# jeu_du_moulin_boura_TouchPAD_SCH.net
KiCad netlist of a schematic drawn in Altium Designer
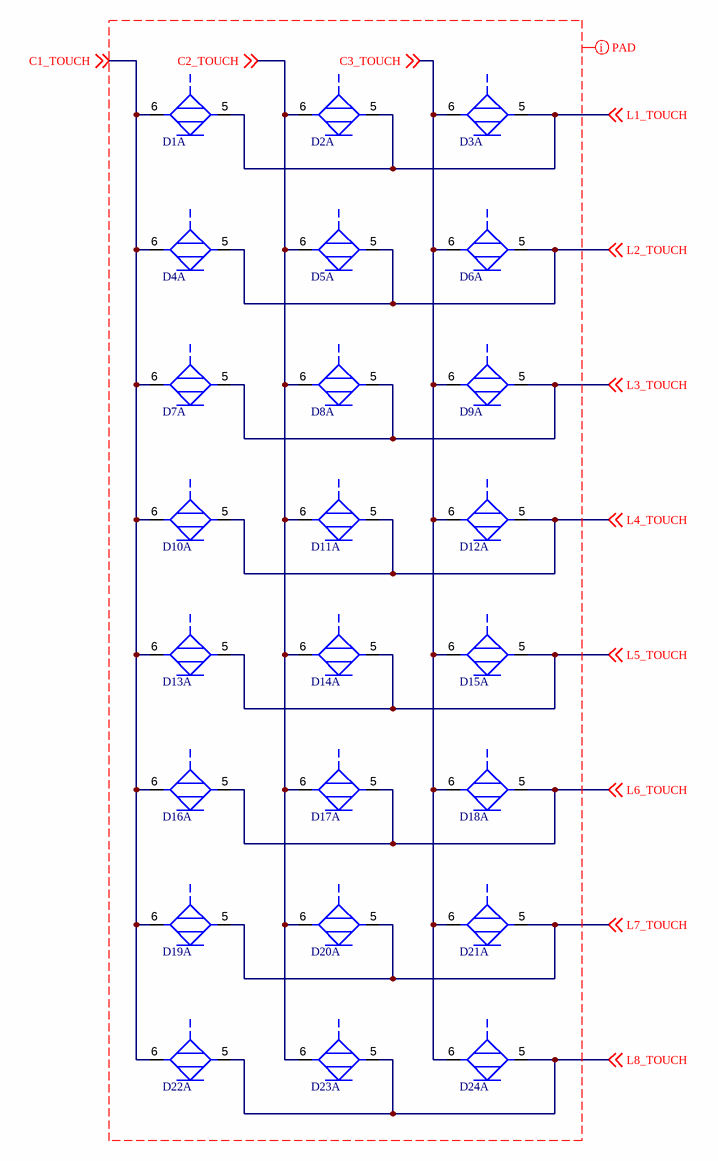
[diagram p0: jeu_du_moulin_boura_TouchPAD_SCH.SchDoc]

(export (version "E")
  (design (tool "Eeschema 10.0.6"))
  (components
    (comp (ref "D1")
      (value "AAA3528SURKCGKC09")
      (footprint "TouchPAD-8mm+LED 4-SMD CIR")
      (libsource (lib "jeu_du_moulin_boura_INTLIB") (part "TouchPAD-BILED4SMD"))
    )
    (comp (ref "D2")
      (value "AAA3528SURKCGKC09")
      (footprint "TouchPAD-8mm+LED 4-SMD CIR")
      (libsource (lib "jeu_du_moulin_boura_INTLIB") (part "TouchPAD-BILED4SMD"))
    )
    (comp (ref "D3")
      (value "AAA3528SURKCGKC09")
      (footprint "TouchPAD-8mm+LED 4-SMD CIR")
      (libsource (lib "jeu_du_moulin_boura_INTLIB") (part "TouchPAD-BILED4SMD"))
    )
    (comp (ref "D4")
      (value "AAA3528SURKCGKC09")
      (footprint "TouchPAD-8mm+LED 4-SMD CIR")
      (libsource (lib "jeu_du_moulin_boura_INTLIB") (part "TouchPAD-BILED4SMD"))
    )
    (comp (ref "D5")
      (value "AAA3528SURKCGKC09")
      (footprint "TouchPAD-8mm+LED 4-SMD CIR")
      (libsource (lib "jeu_du_moulin_boura_INTLIB") (part "TouchPAD-BILED4SMD"))
    )
    (comp (ref "D6")
      (value "AAA3528SURKCGKC09")
      (footprint "TouchPAD-8mm+LED 4-SMD CIR")
      (libsource (lib "jeu_du_moulin_boura_INTLIB") (part "TouchPAD-BILED4SMD"))
    )
    (comp (ref "D7")
      (value "AAA3528SURKCGKC09")
      (footprint "TouchPAD-8mm+LED 4-SMD CIR")
      (libsource (lib "jeu_du_moulin_boura_INTLIB") (part "TouchPAD-BILED4SMD"))
    )
    (comp (ref "D8")
      (value "AAA3528SURKCGKC09")
      (footprint "TouchPAD-8mm+LED 4-SMD CIR")
      (libsource (lib "jeu_du_moulin_boura_INTLIB") (part "TouchPAD-BILED4SMD"))
    )
    (comp (ref "D9")
      (value "AAA3528SURKCGKC09")
      (footprint "TouchPAD-8mm+LED 4-SMD CIR")
      (libsource (lib "jeu_du_moulin_boura_INTLIB") (part "TouchPAD-BILED4SMD"))
    )
    (comp (ref "D10")
      (value "AAA3528SURKCGKC09")
      (footprint "TouchPAD-8mm+LED 4-SMD CIR")
      (libsource (lib "jeu_du_moulin_boura_INTLIB") (part "TouchPAD-BILED4SMD"))
    )
    (comp (ref "D11")
      (value "AAA3528SURKCGKC09")
      (footprint "TouchPAD-8mm+LED 4-SMD CIR")
      (libsource (lib "jeu_du_moulin_boura_INTLIB") (part "TouchPAD-BILED4SMD"))
    )
    (comp (ref "D12")
      (value "AAA3528SURKCGKC09")
      (footprint "TouchPAD-8mm+LED 4-SMD CIR")
      (libsource (lib "jeu_du_moulin_boura_INTLIB") (part "TouchPAD-BILED4SMD"))
    )
    (comp (ref "D13")
      (value "AAA3528SURKCGKC09")
      (footprint "TouchPAD-8mm+LED 4-SMD CIR")
      (libsource (lib "jeu_du_moulin_boura_INTLIB") (part "TouchPAD-BILED4SMD"))
    )
    (comp (ref "D14")
      (value "AAA3528SURKCGKC09")
      (footprint "TouchPAD-8mm+LED 4-SMD CIR")
      (libsource (lib "jeu_du_moulin_boura_INTLIB") (part "TouchPAD-BILED4SMD"))
    )
    (comp (ref "D15")
      (value "AAA3528SURKCGKC09")
      (footprint "TouchPAD-8mm+LED 4-SMD CIR")
      (libsource (lib "jeu_du_moulin_boura_INTLIB") (part "TouchPAD-BILED4SMD"))
    )
    (comp (ref "D16")
      (value "AAA3528SURKCGKC09")
      (footprint "TouchPAD-8mm+LED 4-SMD CIR")
      (libsource (lib "jeu_du_moulin_boura_INTLIB") (part "TouchPAD-BILED4SMD"))
    )
    (comp (ref "D17")
      (value "AAA3528SURKCGKC09")
      (footprint "TouchPAD-8mm+LED 4-SMD CIR")
      (libsource (lib "jeu_du_moulin_boura_INTLIB") (part "TouchPAD-BILED4SMD"))
    )
    (comp (ref "D18")
      (value "AAA3528SURKCGKC09")
      (footprint "TouchPAD-8mm+LED 4-SMD CIR")
      (libsource (lib "jeu_du_moulin_boura_INTLIB") (part "TouchPAD-BILED4SMD"))
    )
    (comp (ref "D19")
      (value "AAA3528SURKCGKC09")
      (footprint "TouchPAD-8mm+LED 4-SMD CIR")
      (libsource (lib "jeu_du_moulin_boura_INTLIB") (part "TouchPAD-BILED4SMD"))
    )
    (comp (ref "D20")
      (value "AAA3528SURKCGKC09")
      (footprint "TouchPAD-8mm+LED 4-SMD CIR")
      (libsource (lib "jeu_du_moulin_boura_INTLIB") (part "TouchPAD-BILED4SMD"))
    )
    (comp (ref "D21")
      (value "AAA3528SURKCGKC09")
      (footprint "TouchPAD-8mm+LED 4-SMD CIR")
      (libsource (lib "jeu_du_moulin_boura_INTLIB") (part "TouchPAD-BILED4SMD"))
    )
    (comp (ref "D22")
      (value "AAA3528SURKCGKC09")
      (footprint "TouchPAD-8mm+LED 4-SMD CIR")
      (libsource (lib "jeu_du_moulin_boura_INTLIB") (part "TouchPAD-BILED4SMD"))
    )
    (comp (ref "D23")
      (value "AAA3528SURKCGKC09")
      (footprint "TouchPAD-8mm+LED 4-SMD CIR")
      (libsource (lib "jeu_du_moulin_boura_INTLIB") (part "TouchPAD-BILED4SMD"))
    )
    (comp (ref "D24")
      (value "AAA3528SURKCGKC09")
      (footprint "TouchPAD-8mm+LED 4-SMD CIR")
      (libsource (lib "jeu_du_moulin_boura_INTLIB") (part "TouchPAD-BILED4SMD"))
    )
  )
  (nets
    (net (code "1") (name "C1_TOUCH") (class "Default")
      (node (ref "D1") (pin "6") (pinfunction "TPAD_6") (pintype "passive"))
      (node (ref "D10") (pin "6") (pinfunction "TPAD_6") (pintype "passive"))
      (node (ref "D13") (pin "6") (pinfunction "TPAD_6") (pintype "passive"))
      (node (ref "D16") (pin "6") (pinfunction "TPAD_6") (pintype "passive"))
      (node (ref "D19") (pin "6") (pinfunction "TPAD_6") (pintype "passive"))
      (node (ref "D22") (pin "6") (pinfunction "TPAD_6") (pintype "passive"))
      (node (ref "D4") (pin "6") (pinfunction "TPAD_6") (pintype "passive"))
      (node (ref "D7") (pin "6") (pinfunction "TPAD_6") (pintype "passive"))
    )
    (net (code "2") (name "C2_TOUCH") (class "Default")
      (node (ref "D11") (pin "6") (pinfunction "TPAD_6") (pintype "passive"))
      (node (ref "D14") (pin "6") (pinfunction "TPAD_6") (pintype "passive"))
      (node (ref "D17") (pin "6") (pinfunction "TPAD_6") (pintype "passive"))
      (node (ref "D2") (pin "6") (pinfunction "TPAD_6") (pintype "passive"))
      (node (ref "D20") (pin "6") (pinfunction "TPAD_6") (pintype "passive"))
      (node (ref "D23") (pin "6") (pinfunction "TPAD_6") (pintype "passive"))
      (node (ref "D5") (pin "6") (pinfunction "TPAD_6") (pintype "passive"))
      (node (ref "D8") (pin "6") (pinfunction "TPAD_6") (pintype "passive"))
    )
    (net (code "3") (name "C3_TOUCH") (class "Default")
      (node (ref "D12") (pin "6") (pinfunction "TPAD_6") (pintype "passive"))
      (node (ref "D15") (pin "6") (pinfunction "TPAD_6") (pintype "passive"))
      (node (ref "D18") (pin "6") (pinfunction "TPAD_6") (pintype "passive"))
      (node (ref "D21") (pin "6") (pinfunction "TPAD_6") (pintype "passive"))
      (node (ref "D24") (pin "6") (pinfunction "TPAD_6") (pintype "passive"))
      (node (ref "D3") (pin "6") (pinfunction "TPAD_6") (pintype "passive"))
      (node (ref "D6") (pin "6") (pinfunction "TPAD_6") (pintype "passive"))
      (node (ref "D9") (pin "6") (pinfunction "TPAD_6") (pintype "passive"))
    )
    (net (code "4") (name "L1_TOUCH") (class "Default")
      (node (ref "D1") (pin "5") (pinfunction "TPAD_5") (pintype "passive"))
      (node (ref "D2") (pin "5") (pinfunction "TPAD_5") (pintype "passive"))
      (node (ref "D3") (pin "5") (pinfunction "TPAD_5") (pintype "passive"))
    )
    (net (code "5") (name "L2_TOUCH") (class "Default")
      (node (ref "D4") (pin "5") (pinfunction "TPAD_5") (pintype "passive"))
      (node (ref "D5") (pin "5") (pinfunction "TPAD_5") (pintype "passive"))
      (node (ref "D6") (pin "5") (pinfunction "TPAD_5") (pintype "passive"))
    )
    (net (code "6") (name "L3_TOUCH") (class "Default")
      (node (ref "D7") (pin "5") (pinfunction "TPAD_5") (pintype "passive"))
      (node (ref "D8") (pin "5") (pinfunction "TPAD_5") (pintype "passive"))
      (node (ref "D9") (pin "5") (pinfunction "TPAD_5") (pintype "passive"))
    )
    (net (code "7") (name "L4_TOUCH") (class "Default")
      (node (ref "D10") (pin "5") (pinfunction "TPAD_5") (pintype "passive"))
      (node (ref "D11") (pin "5") (pinfunction "TPAD_5") (pintype "passive"))
      (node (ref "D12") (pin "5") (pinfunction "TPAD_5") (pintype "passive"))
    )
    (net (code "8") (name "L5_TOUCH") (class "Default")
      (node (ref "D13") (pin "5") (pinfunction "TPAD_5") (pintype "passive"))
      (node (ref "D14") (pin "5") (pinfunction "TPAD_5") (pintype "passive"))
      (node (ref "D15") (pin "5") (pinfunction "TPAD_5") (pintype "passive"))
    )
    (net (code "9") (name "L6_TOUCH") (class "Default")
      (node (ref "D16") (pin "5") (pinfunction "TPAD_5") (pintype "passive"))
      (node (ref "D17") (pin "5") (pinfunction "TPAD_5") (pintype "passive"))
      (node (ref "D18") (pin "5") (pinfunction "TPAD_5") (pintype "passive"))
    )
    (net (code "10") (name "L7_TOUCH") (class "Default")
      (node (ref "D19") (pin "5") (pinfunction "TPAD_5") (pintype "passive"))
      (node (ref "D20") (pin "5") (pinfunction "TPAD_5") (pintype "passive"))
      (node (ref "D21") (pin "5") (pinfunction "TPAD_5") (pintype "passive"))
    )
    (net (code "11") (name "L8_TOUCH") (class "Default")
      (node (ref "D22") (pin "5") (pinfunction "TPAD_5") (pintype "passive"))
      (node (ref "D23") (pin "5") (pinfunction "TPAD_5") (pintype "passive"))
      (node (ref "D24") (pin "5") (pinfunction "TPAD_5") (pintype "passive"))
    )
  )
)
